# FOX_HTOL_test_1_0.net
KiCad netlist of a schematic drawn in EasyEDA Pro
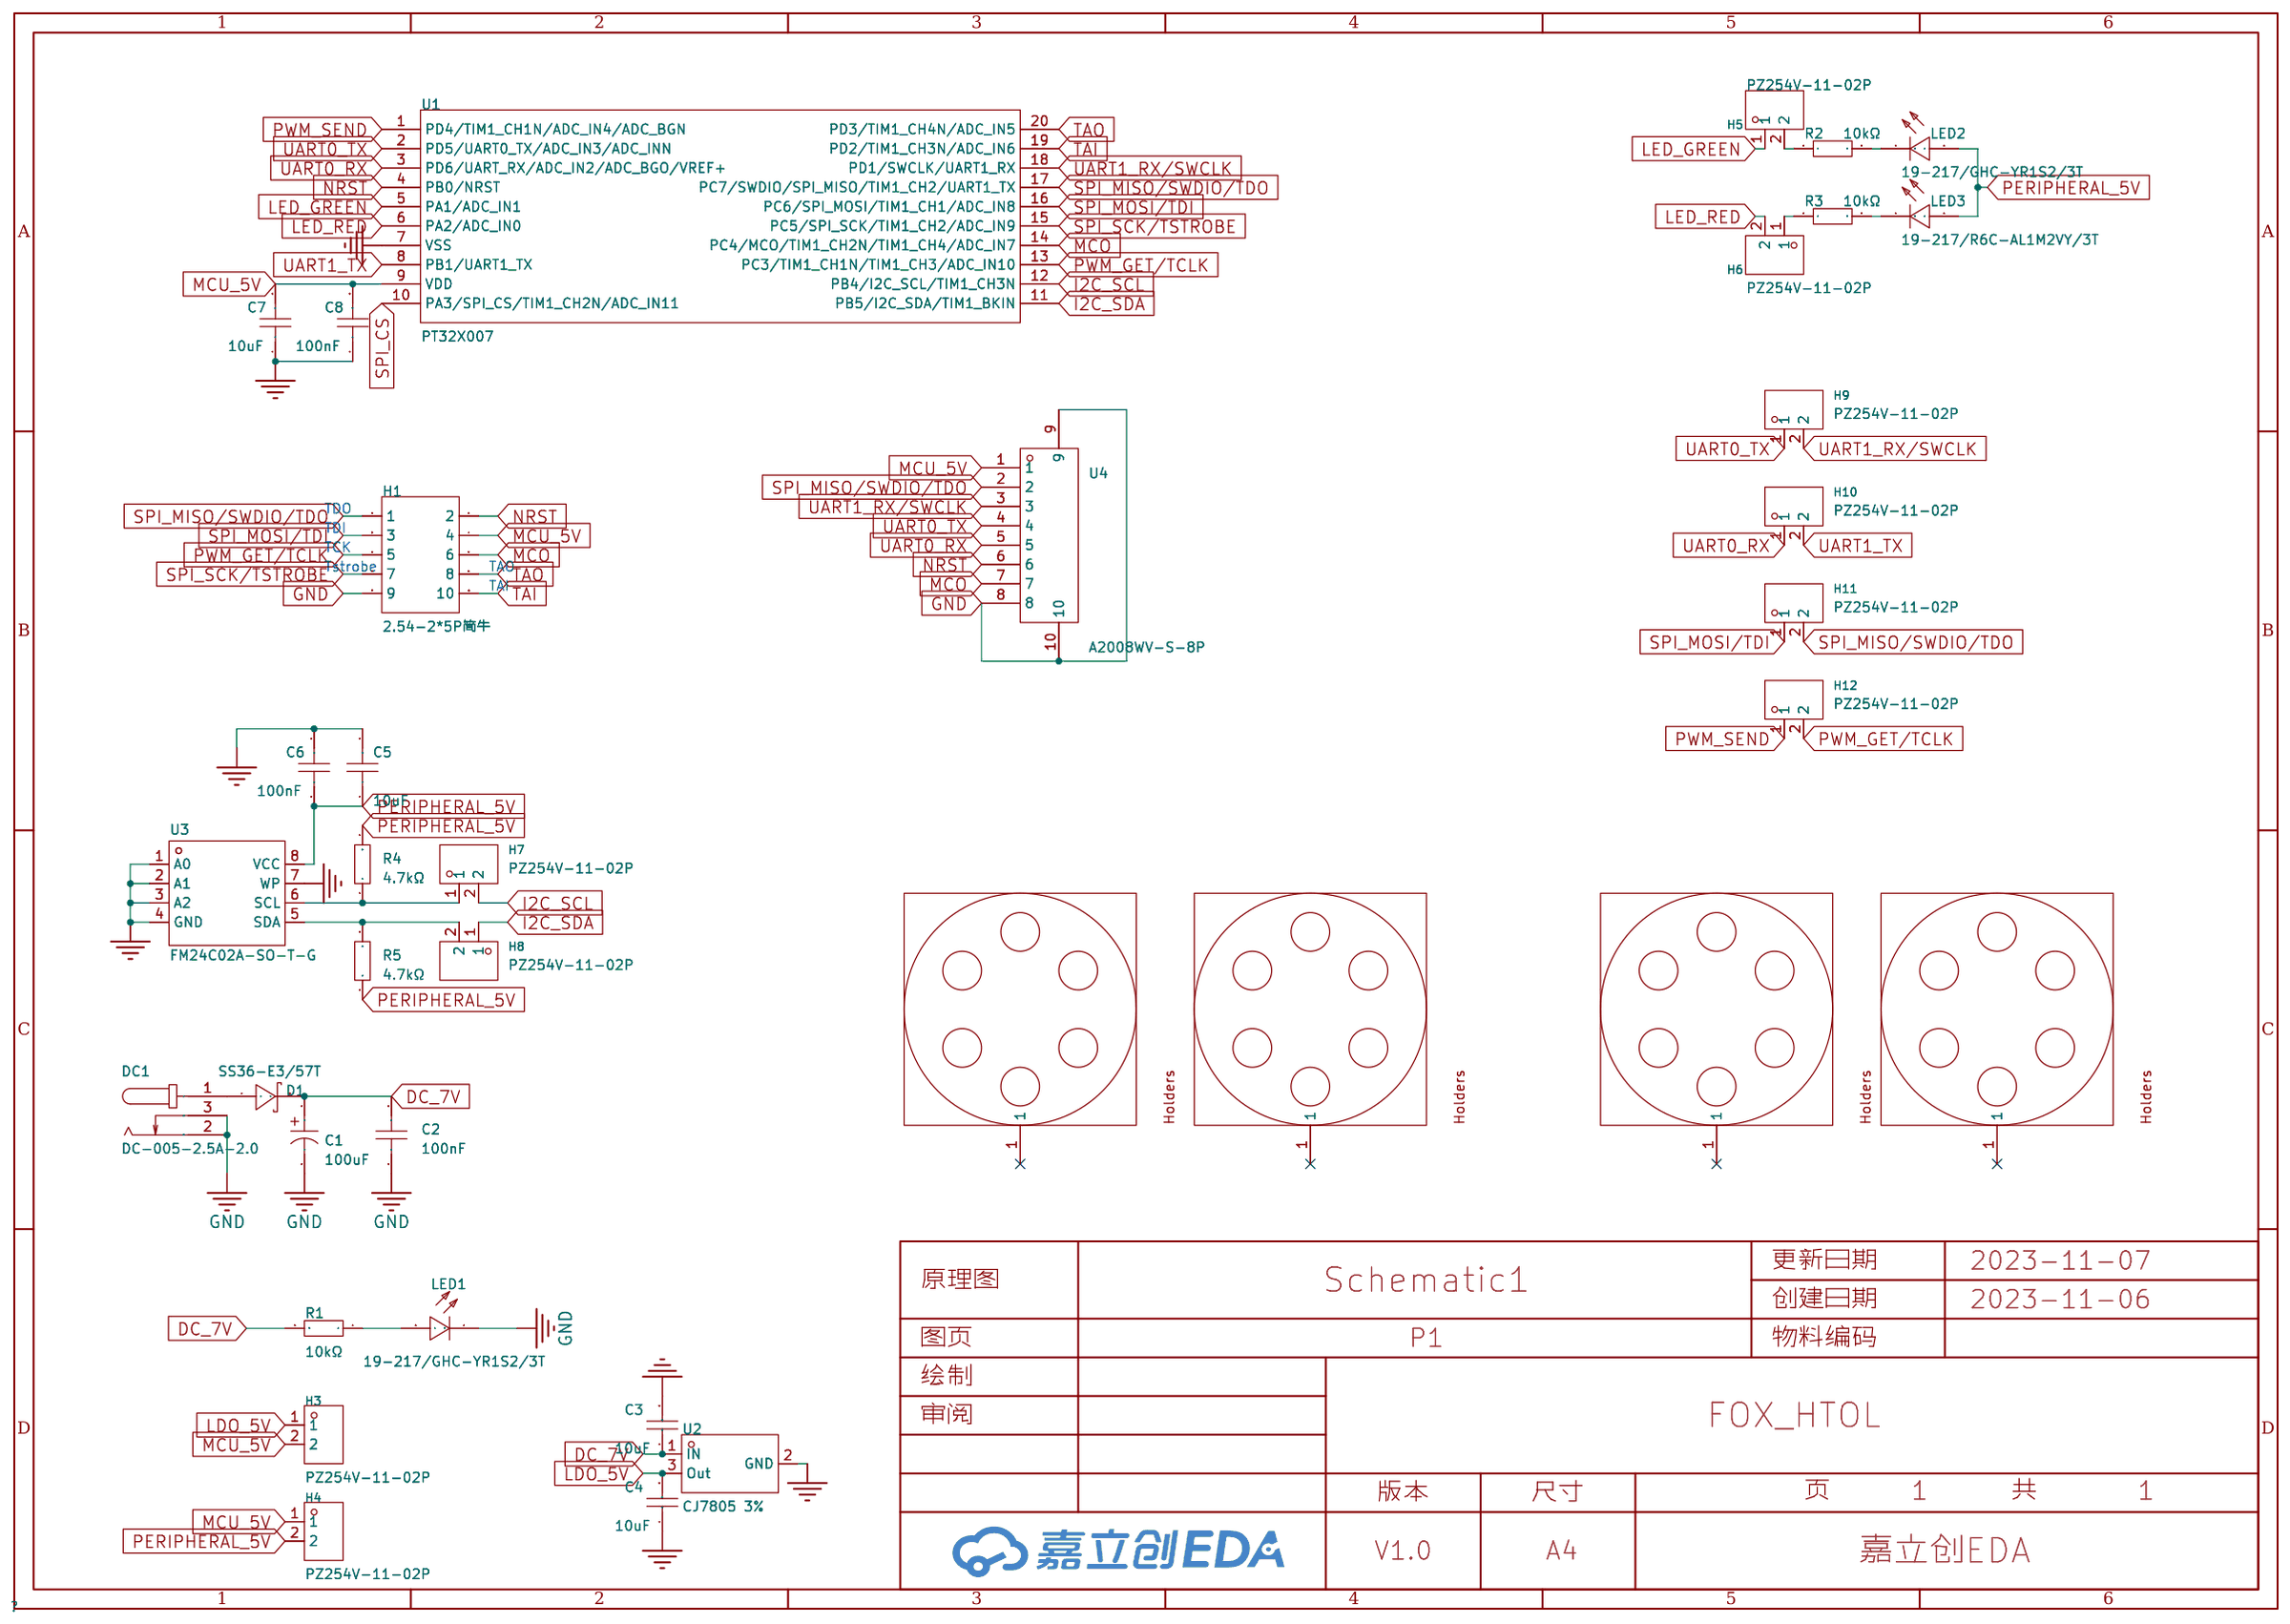
[diagram p0: schematic sheet]

(export (version "E")
  (design (tool "Eeschema 10.0.6"))
  (components
    (comp (ref "C1")
      (value "100uF")
      (footprint "easyedapro:CAP-SMD_BD6.3-L6.6-W6.6-LS7.6-FD-1")
      (description "容值:100uF;额定电压:35V;电容体直径:-;电容体长度:-;纹波电流:-;等效串联电阻:-;工作寿命:-;")
      (fields
        (field (name "Manufacturer Part") "RVE100UF35V67RV0072")
        (field (name "Manufacturer") "KNSCHA(科尼盛)")
      )
      (libsource (lib "easyedapro") (part "RVE100UF35V67RV0072"))
    )
    (comp (ref "C2")
      (value "100nF")
      (footprint "easyedapro:C0603")
      (description "容值:100nF;精度:±10%;额定电压:50V;材质(温度系数):X7R;")
      (fields
        (field (name "Manufacturer Part") "CL10B104KB8NNNC")
        (field (name "Manufacturer") "SAMSUNG(三星)")
      )
      (libsource (lib "easyedapro") (part "CL10B104KB8NNNC"))
    )
    (comp (ref "C3")
      (value "10uF")
      (footprint "easyedapro:C1206")
      (description "容值:10uF;精度:±10%;额定电压:50V;材质(温度系数):X5R;")
      (fields
        (field (name "Manufacturer Part") "CL31A106KBHNNNE")
        (field (name "Manufacturer") "SAMSUNG(三星)")
      )
      (libsource (lib "easyedapro") (part "CL31A106KBHNNNE"))
    )
    (comp (ref "C4")
      (value "10uF")
      (footprint "easyedapro:C1206")
      (description "容值:10uF;精度:±10%;额定电压:50V;材质(温度系数):X5R;")
      (fields
        (field (name "Manufacturer Part") "CL31A106KBHNNNE")
        (field (name "Manufacturer") "SAMSUNG(三星)")
      )
      (libsource (lib "easyedapro") (part "CL31A106KBHNNNE"))
    )
    (comp (ref "C5")
      (value "10uF")
      (footprint "easyedapro:C0603")
      (description "容值:10uF;精度:±20%;额定电压:25V;材质(温度系数):X5R;")
      (fields
        (field (name "Manufacturer Part") "CL10A106MA8NRNC")
        (field (name "Manufacturer") "SAMSUNG(三星)")
      )
      (libsource (lib "easyedapro") (part "CL10A106MA8NRNC"))
    )
    (comp (ref "C6")
      (value "100nF")
      (footprint "easyedapro:C0603")
      (description "容值:100nF;精度:±10%;额定电压:50V;材质(温度系数):X7R;")
      (fields
        (field (name "Manufacturer Part") "CC0603KRX7R9BB104")
        (field (name "Manufacturer") "YAGEO(国巨)")
      )
      (libsource (lib "easyedapro") (part "CC0603KRX7R9BB104"))
    )
    (comp (ref "C7")
      (value "10uF")
      (footprint "easyedapro:C0603")
      (description "容值:10uF;精度:±20%;额定电压:25V;材质(温度系数):X5R;")
      (fields
        (field (name "Manufacturer Part") "CL10A106MA8NRNC")
        (field (name "Manufacturer") "SAMSUNG(三星)")
      )
      (libsource (lib "easyedapro") (part "CL10A106MA8NRNC"))
    )
    (comp (ref "C8")
      (value "100nF")
      (footprint "easyedapro:C0603")
      (description "容值:100nF;精度:±10%;额定电压:50V;材质(温度系数):X7R;")
      (fields
        (field (name "Manufacturer Part") "CC0603KRX7R9BB104")
        (field (name "Manufacturer") "YAGEO(国巨)")
      )
      (libsource (lib "easyedapro") (part "CC0603KRX7R9BB104"))
    )
    (comp (ref "D1")
      (value "SS36-E3/57T")
      (footprint "easyedapro:SMC_L7.1-W6.2-LS8.1-R-RD")
      (description "直流反向耐压（Vr）:60V;平均整流电流（Io）:3A;正向压降（Vf）:750mV @ 3A;")
      (fields (field (name "Manufacturer") "VISHAY(威世)"))
      (libsource (lib "easyedapro") (part "SS36-E3/57T"))
    )
    (comp (ref "DC1")
      (value "DC-005-2.5A-2.0")
      (footprint "easyedapro:CONN-TH_DC-005-2.5A-2.0")
      (fields (field (name "Manufacturer") "XKB Connectivity(中国星坤)"))
      (libsource (lib "easyedapro") (part "DC-005-2.5A-2.0"))
    )
    (comp (ref "H1")
      (value "2.54-2*5P简牛")
      (footprint "easyedapro:IDC-TH_10P-P2.54_C5665")
      (description "连接器类型:简牛座;每排PIN数:5;排数:2;间距:2.54mm;行距:2.54mm;封装形式:直插;触头材质:-;触头镀层:-;")
      (fields (field (name "Manufacturer") "BOOMELE(博穆精密)"))
      (libsource (lib "easyedapro") (part "HDR-IDC-2.54-2X5P"))
    )
    (comp (ref "H3")
      (value "PZ254V-11-02P")
      (footprint "easyedapro:HDR-TH_2P-P2.54-V-M")
      (fields (field (name "Manufacturer") "XFCN(兴飞)"))
      (libsource (lib "easyedapro") (part "PZ254V-11-02P"))
    )
    (comp (ref "H4")
      (value "PZ254V-11-02P")
      (footprint "easyedapro:HDR-TH_2P-P2.54-V-M")
      (fields (field (name "Manufacturer") "XFCN(兴飞)"))
      (libsource (lib "easyedapro") (part "PZ254V-11-02P"))
    )
    (comp (ref "H5")
      (value "PZ254V-11-02P")
      (footprint "easyedapro:HDR-TH_2P-P2.54-V-M")
      (fields (field (name "Manufacturer") "XFCN(兴飞)"))
      (libsource (lib "easyedapro") (part "PZ254V-11-02P"))
    )
    (comp (ref "H6")
      (value "PZ254V-11-02P")
      (footprint "easyedapro:HDR-TH_2P-P2.54-V-M")
      (fields (field (name "Manufacturer") "XFCN(兴飞)"))
      (libsource (lib "easyedapro") (part "PZ254V-11-02P"))
    )
    (comp (ref "H7")
      (value "PZ254V-11-02P")
      (footprint "easyedapro:HDR-TH_2P-P2.54-V-M")
      (fields (field (name "Manufacturer") "XFCN(兴飞)"))
      (libsource (lib "easyedapro") (part "PZ254V-11-02P"))
    )
    (comp (ref "H8")
      (value "PZ254V-11-02P")
      (footprint "easyedapro:HDR-TH_2P-P2.54-V-M")
      (fields (field (name "Manufacturer") "XFCN(兴飞)"))
      (libsource (lib "easyedapro") (part "PZ254V-11-02P"))
    )
    (comp (ref "H9")
      (value "PZ254V-11-02P")
      (footprint "easyedapro:HDR-TH_2P-P2.54-V-M")
      (fields (field (name "Manufacturer") "XFCN(兴飞)"))
      (libsource (lib "easyedapro") (part "PZ254V-11-02P"))
    )
    (comp (ref "H10")
      (value "PZ254V-11-02P")
      (footprint "easyedapro:HDR-TH_2P-P2.54-V-M")
      (fields (field (name "Manufacturer") "XFCN(兴飞)"))
      (libsource (lib "easyedapro") (part "PZ254V-11-02P"))
    )
    (comp (ref "H11")
      (value "PZ254V-11-02P")
      (footprint "easyedapro:HDR-TH_2P-P2.54-V-M")
      (fields (field (name "Manufacturer") "XFCN(兴飞)"))
      (libsource (lib "easyedapro") (part "PZ254V-11-02P"))
    )
    (comp (ref "H12")
      (value "PZ254V-11-02P")
      (footprint "easyedapro:HDR-TH_2P-P2.54-V-M")
      (fields (field (name "Manufacturer") "XFCN(兴飞)"))
      (libsource (lib "easyedapro") (part "PZ254V-11-02P"))
    )
    (comp (ref "J2")
      (value "~")
      (footprint "easyedapro:DEMO板安装孔")
      (libsource (lib "easyedapro") (part "螺孔_3.1X6MM"))
    )
    (comp (ref "J3")
      (value "~")
      (footprint "easyedapro:DEMO板安装孔")
      (libsource (lib "easyedapro") (part "螺孔_3.1X6MM"))
    )
    (comp (ref "J4")
      (value "~")
      (footprint "easyedapro:DEMO板安装孔")
      (libsource (lib "easyedapro") (part "螺孔_3.1X6MM"))
    )
    (comp (ref "J5")
      (value "~")
      (footprint "easyedapro:DEMO板安装孔")
      (libsource (lib "easyedapro") (part "螺孔_3.1X6MM"))
    )
    (comp (ref "LED1")
      (value "19-217/GHC-YR1S2/3T")
      (footprint "easyedapro:LED0603-RD")
      (fields (field (name "Manufacturer") "EVERLIGHT(亿光)"))
      (libsource (lib "easyedapro") (part "19-217/GHC-YR1S2/3T"))
    )
    (comp (ref "LED2")
      (value "19-217/GHC-YR1S2/3T")
      (footprint "easyedapro:LED0603-RD")
      (fields (field (name "Manufacturer") "EVERLIGHT(亿光)"))
      (libsource (lib "easyedapro") (part "19-217/GHC-YR1S2/3T"))
    )
    (comp (ref "LED3")
      (value "19-217/R6C-AL1M2VY/3T")
      (footprint "easyedapro:LED0603-RD")
      (description "发光颜色:红灯;二极管配置:-;透镜颜色:无色透明;主波长:617.5nm;色温:-;功率:60mW;发光角度:120°;安装方式:-;工作温度:-40°C~+85°C;")
      (fields (field (name "Manufacturer") "EVERLIGHT(亿光)"))
      (libsource (lib "easyedapro") (part "19-217/R6C-AL1M2VY/3T"))
    )
    (comp (ref "R1")
      (value "10kΩ")
      (footprint "easyedapro:R0603")
      (description "电阻类型:厚膜电阻;阻值:10kΩ;精度:±1%;功率:100mW;温度系数:±100ppm/℃;最大工作电压:75V;工作温度范围:-55℃~+155℃;")
      (fields
        (field (name "Manufacturer Part") "0603WAF1002T5E")
        (field (name "Manufacturer") "UNI-ROYAL(厚声)")
      )
      (libsource (lib "easyedapro") (part "0603WAF1002T5E"))
    )
    (comp (ref "R2")
      (value "10kΩ")
      (footprint "easyedapro:R0603")
      (description "电阻类型:厚膜电阻;阻值:10kΩ;精度:±1%;功率:100mW;")
      (fields
        (field (name "Manufacturer Part") "0603WAF1002T5E")
        (field (name "Manufacturer") "UNI-ROYAL(厚声)")
      )
      (libsource (lib "easyedapro") (part "0603WAF1002T5E"))
    )
    (comp (ref "R3")
      (value "10kΩ")
      (footprint "easyedapro:R0603")
      (description "电阻类型:厚膜电阻;阻值:10kΩ;精度:±1%;功率:100mW;")
      (fields
        (field (name "Manufacturer Part") "0603WAF1002T5E")
        (field (name "Manufacturer") "UNI-ROYAL(厚声)")
      )
      (libsource (lib "easyedapro") (part "0603WAF1002T5E"))
    )
    (comp (ref "R4")
      (value "4.7kΩ")
      (footprint "easyedapro:R0603")
      (description "电阻类型:厚膜电阻;阻值:4.7kΩ;精度:±1%;功率:100mW;温度系数:±100ppm/°C;")
      (fields
        (field (name "Manufacturer Part") "0603WAF4701T5E")
        (field (name "Manufacturer") "UNI-ROYAL(厚声)")
      )
      (libsource (lib "easyedapro") (part "0603WAF4701T5E"))
    )
    (comp (ref "R5")
      (value "4.7kΩ")
      (footprint "easyedapro:R0603")
      (description "电阻类型:厚膜电阻;阻值:4.7kΩ;精度:±1%;功率:100mW;温度系数:±100ppm/°C;")
      (fields
        (field (name "Manufacturer Part") "0603WAF4701T5E")
        (field (name "Manufacturer") "UNI-ROYAL(厚声)")
      )
      (libsource (lib "easyedapro") (part "0603WAF4701T5E"))
    )
    (comp (ref "U1")
      (value "PT32X007")
      (footprint "easyedapro:TSSOP-20_L6.5-W4.4-P0.65-LS6.4-BL")
      (libsource (lib "easyedapro") (part "PT32X007"))
    )
    (comp (ref "U2")
      (value "CJ7805 3%")
      (footprint "easyedapro:TO-252-2_L6.6-W6.1-P4.58-LS10.1-BR-CW")
      (description "输出类型:固定;输出极性:正;最大输入电压:35V;输出电压:5V;输出电流:1.5A;")
      (fields (field (name "Manufacturer") "CJ(江苏长电/长晶)"))
      (libsource (lib "easyedapro") (part "CJ7805 3%"))
    )
    (comp (ref "U3")
      (value "FM24C02A-SO-T-G")
      (footprint "easyedapro:SOP-8_L5.0-W4.0-P1.27-LS6.2-BL")
      (description "2-Kbit(256 x 8bit)，I2C接口，工作电压：1.7V to 5.5V")
      (fields (field (name "Manufacturer") "FM(复旦微)"))
      (libsource (lib "easyedapro") (part "FM24C02A-SO-TR"))
    )
    (comp (ref "U4")
      (value "A2008WV-S-8P")
      (footprint "easyedapro:CONN-SMD_A2008WV-S-8P")
      (description "参考系列:PH;间距:2mm;插针结构:1x8P;排数:1;每排PIN数:8;行距:-;安装方式:-;触头材质:黄铜;")
      (fields (field (name "Manufacturer") "CJT(长江连接器)"))
      (libsource (lib "easyedapro") (part "A2008WV-S-8P"))
    )
  )
  (nets
    (net (code "1") (name "DC_7V") (class "Default")
      (node (ref "C1") (pin "1") (pinfunction "1_1") (pintype "input"))
      (node (ref "C2") (pin "2") (pinfunction "2_2") (pintype "input"))
      (node (ref "C3") (pin "1") (pinfunction "1_1") (pintype "input"))
      (node (ref "D1") (pin "2") (pinfunction "K_2") (pintype "input"))
      (node (ref "R1") (pin "2") (pinfunction "2_2") (pintype "input"))
      (node (ref "U2") (pin "1") (pinfunction "IN_1") (pintype "input"))
    )
    (net (code "2") (name "GND") (class "Default")
      (node (ref "C1") (pin "2") (pinfunction "2_2") (pintype "input"))
      (node (ref "C2") (pin "1") (pinfunction "1_1") (pintype "input"))
      (node (ref "C3") (pin "2") (pinfunction "2_2") (pintype "input"))
      (node (ref "C4") (pin "1") (pinfunction "1_1") (pintype "input"))
      (node (ref "C5") (pin "2") (pinfunction "2_2") (pintype "input"))
      (node (ref "C6") (pin "2") (pinfunction "2_2") (pintype "input"))
      (node (ref "C7") (pin "1") (pinfunction "1_1") (pintype "input"))
      (node (ref "C8") (pin "1") (pinfunction "1_1") (pintype "input"))
      (node (ref "DC1") (pin "2") (pinfunction "2_2") (pintype "input"))
      (node (ref "DC1") (pin "3") (pinfunction "3_3") (pintype "input"))
      (node (ref "H1") (pin "9") (pinfunction "9_9") (pintype "input"))
      (node (ref "LED1") (pin "1") (pinfunction "C_1") (pintype "input"))
      (node (ref "U1") (pin "7") (pinfunction "VSS_7") (pintype "input"))
      (node (ref "U2") (pin "2") (pinfunction "GND_2") (pintype "input"))
      (node (ref "U3") (pin "1") (pinfunction "A0_1") (pintype "unspecified"))
      (node (ref "U3") (pin "2") (pinfunction "A1_2") (pintype "unspecified"))
      (node (ref "U3") (pin "3") (pinfunction "A2_3") (pintype "unspecified"))
      (node (ref "U3") (pin "4") (pinfunction "GND_4") (pintype "unspecified"))
      (node (ref "U3") (pin "7") (pinfunction "WP_7") (pintype "unspecified"))
      (node (ref "U4") (pin "10") (pinfunction "10_10") (pintype "input"))
      (node (ref "U4") (pin "8") (pinfunction "8_8") (pintype "input"))
      (node (ref "U4") (pin "9") (pinfunction "9_9") (pintype "input"))
    )
    (net (code "3") (name "I2C_SCL") (class "Default")
      (node (ref "H7") (pin "2") (pinfunction "2_2") (pintype "input"))
      (node (ref "U1") (pin "12") (pinfunction "PB4/I2C_SCL/TIM1_CH3N_12") (pintype "input"))
    )
    (net (code "4") (name "I2C_SDA") (class "Default")
      (node (ref "H8") (pin "1") (pinfunction "1_1") (pintype "input"))
      (node (ref "U1") (pin "11") (pinfunction "PB5/I2C_SDA/TIM1_BKIN_11") (pintype "input"))
    )
    (net (code "5") (name "LDO_5V") (class "Default")
      (node (ref "C4") (pin "2") (pinfunction "2_2") (pintype "input"))
      (node (ref "H3") (pin "1") (pinfunction "1_1") (pintype "input"))
      (node (ref "U2") (pin "3") (pinfunction "Out_3") (pintype "input"))
    )
    (net (code "6") (name "LED_GREEN") (class "Default")
      (node (ref "H5") (pin "1") (pinfunction "1_1") (pintype "input"))
      (node (ref "U1") (pin "5") (pinfunction "PA1/ADC_IN1_5") (pintype "input"))
    )
    (net (code "7") (name "LED_RED") (class "Default")
      (node (ref "H6") (pin "2") (pinfunction "2_2") (pintype "input"))
      (node (ref "U1") (pin "6") (pinfunction "PA2/ADC_IN0_6") (pintype "input"))
    )
    (net (code "8") (name "MCO") (class "Default")
      (node (ref "H1") (pin "6") (pinfunction "6_6") (pintype "input"))
      (node (ref "U1") (pin "14") (pinfunction "PC4/MCO/TIM1_CH2N/TIM1_CH4/ADC_IN7_14") (pintype "input"))
      (node (ref "U4") (pin "7") (pinfunction "7_7") (pintype "input"))
    )
    (net (code "9") (name "MCU_5V") (class "Default")
      (node (ref "C7") (pin "2") (pinfunction "2_2") (pintype "input"))
      (node (ref "C8") (pin "2") (pinfunction "2_2") (pintype "input"))
      (node (ref "H1") (pin "4") (pinfunction "4_4") (pintype "input"))
      (node (ref "H3") (pin "2") (pinfunction "2_2") (pintype "input"))
      (node (ref "H4") (pin "1") (pinfunction "1_1") (pintype "input"))
      (node (ref "U1") (pin "9") (pinfunction "VDD_9") (pintype "input"))
      (node (ref "U4") (pin "1") (pinfunction "1_1") (pintype "input"))
    )
    (net (code "10") (name "NRST") (class "Default")
      (node (ref "H1") (pin "2") (pinfunction "2_2") (pintype "input"))
      (node (ref "U1") (pin "4") (pinfunction "PB0/NRST_4") (pintype "input"))
      (node (ref "U4") (pin "6") (pinfunction "6_6") (pintype "input"))
    )
    (net (code "11") (name "Net-(D1-A)") (class "Default")
      (node (ref "D1") (pin "1") (pinfunction "A_1") (pintype "input"))
      (node (ref "DC1") (pin "1") (pinfunction "1_1") (pintype "input"))
    )
    (net (code "12") (name "Net-(H5-Pad2)") (class "Default")
      (node (ref "H5") (pin "2") (pinfunction "2_2") (pintype "input"))
      (node (ref "R2") (pin "1") (pinfunction "1_1") (pintype "input"))
    )
    (net (code "13") (name "Net-(H6-Pad1)") (class "Default")
      (node (ref "H6") (pin "1") (pinfunction "1_1") (pintype "input"))
      (node (ref "R3") (pin "1") (pinfunction "1_1") (pintype "input"))
    )
    (net (code "14") (name "Net-(LED1-A)") (class "Default")
      (node (ref "LED1") (pin "2") (pinfunction "A_2") (pintype "input"))
      (node (ref "R1") (pin "1") (pinfunction "1_1") (pintype "input"))
    )
    (net (code "15") (name "Net-(LED2-C)") (class "Default")
      (node (ref "LED2") (pin "1") (pinfunction "C_1") (pintype "input"))
      (node (ref "R2") (pin "2") (pinfunction "2_2") (pintype "input"))
    )
    (net (code "16") (name "Net-(LED3-C)") (class "Default")
      (node (ref "LED3") (pin "1") (pinfunction "C_1") (pintype "input"))
      (node (ref "R3") (pin "2") (pinfunction "2_2") (pintype "input"))
    )
    (net (code "17") (name "Net-(U3-SCL)") (class "Default")
      (node (ref "H7") (pin "1") (pinfunction "1_1") (pintype "input"))
      (node (ref "R4") (pin "1") (pinfunction "1_1") (pintype "input"))
      (node (ref "U3") (pin "6") (pinfunction "SCL_6") (pintype "unspecified"))
    )
    (net (code "18") (name "Net-(U3-SDA)") (class "Default")
      (node (ref "H8") (pin "2") (pinfunction "2_2") (pintype "input"))
      (node (ref "R5") (pin "2") (pinfunction "2_2") (pintype "input"))
      (node (ref "U3") (pin "5") (pinfunction "SDA_5") (pintype "unspecified"))
    )
    (net (code "19") (name "PERIPHERAL_5V") (class "Default")
      (node (ref "C5") (pin "1") (pinfunction "1_1") (pintype "input"))
      (node (ref "C6") (pin "1") (pinfunction "1_1") (pintype "input"))
      (node (ref "H4") (pin "2") (pinfunction "2_2") (pintype "input"))
      (node (ref "LED2") (pin "2") (pinfunction "A_2") (pintype "input"))
      (node (ref "LED3") (pin "2") (pinfunction "A_2") (pintype "input"))
      (node (ref "R4") (pin "2") (pinfunction "2_2") (pintype "input"))
      (node (ref "R5") (pin "1") (pinfunction "1_1") (pintype "input"))
      (node (ref "U3") (pin "8") (pinfunction "VCC_8") (pintype "unspecified"))
    )
    (net (code "20") (name "PWM_GET{slash}TCLK") (class "Default")
      (node (ref "H1") (pin "5") (pinfunction "5_5") (pintype "input"))
      (node (ref "H12") (pin "2") (pinfunction "2_2") (pintype "input"))
      (node (ref "U1") (pin "13") (pinfunction "PC3/TIM1_CH1N/TIM1_CH3/ADC_IN10_13") (pintype "input"))
    )
    (net (code "21") (name "PWM_SEND") (class "Default")
      (node (ref "H12") (pin "1") (pinfunction "1_1") (pintype "input"))
      (node (ref "U1") (pin "1") (pinfunction "PD4/TIM1_CH1N/ADC_IN4/ADC_BGN_1") (pintype "input"))
    )
    (net (code "22") (name "SPI_CS") (class "Default")
      (node (ref "U1") (pin "10") (pinfunction "PA3/SPI_CS/TIM1_CH2N/ADC_IN11_10") (pintype "input"))
    )
    (net (code "23") (name "SPI_MISO{slash}SWDIO{slash}TDO") (class "Default")
      (node (ref "H1") (pin "1") (pinfunction "1_1") (pintype "input"))
      (node (ref "H11") (pin "2") (pinfunction "2_2") (pintype "input"))
      (node (ref "U1") (pin "17") (pinfunction "PC7/SWDIO/SPI_MISO/TIM1_CH2/UART1_TX_17") (pintype "input"))
      (node (ref "U4") (pin "2") (pinfunction "2_2") (pintype "input"))
    )
    (net (code "24") (name "SPI_MOSI{slash}TDI") (class "Default")
      (node (ref "H1") (pin "3") (pinfunction "3_3") (pintype "input"))
      (node (ref "H11") (pin "1") (pinfunction "1_1") (pintype "input"))
      (node (ref "U1") (pin "16") (pinfunction "PC6/SPI_MOSI/TIM1_CH1/ADC_IN8_16") (pintype "input"))
    )
    (net (code "25") (name "SPI_SCK{slash}TSTROBE") (class "Default")
      (node (ref "H1") (pin "7") (pinfunction "7_7") (pintype "input"))
      (node (ref "U1") (pin "15") (pinfunction "PC5/SPI_SCK/TIM1_CH2/ADC_IN9_15") (pintype "input"))
    )
    (net (code "26") (name "TAI") (class "Default")
      (node (ref "H1") (pin "10") (pinfunction "10_10") (pintype "input"))
      (node (ref "U1") (pin "19") (pinfunction "PD2/TIM1_CH3N/ADC_IN6_19") (pintype "input"))
    )
    (net (code "27") (name "TAO") (class "Default")
      (node (ref "H1") (pin "8") (pinfunction "8_8") (pintype "input"))
      (node (ref "U1") (pin "20") (pinfunction "PD3/TIM1_CH4N/ADC_IN5_20") (pintype "input"))
    )
    (net (code "28") (name "UART0_RX") (class "Default")
      (node (ref "H10") (pin "1") (pinfunction "1_1") (pintype "input"))
      (node (ref "U1") (pin "3") (pinfunction "PD6/UART_RX/ADC_IN2/ADC_BGO/VREF+_3") (pintype "input"))
      (node (ref "U4") (pin "5") (pinfunction "5_5") (pintype "input"))
    )
    (net (code "29") (name "UART0_TX") (class "Default")
      (node (ref "H9") (pin "1") (pinfunction "1_1") (pintype "input"))
      (node (ref "U1") (pin "2") (pinfunction "PD5/UART0_TX/ADC_IN3/ADC_INN_2") (pintype "input"))
      (node (ref "U4") (pin "4") (pinfunction "4_4") (pintype "input"))
    )
    (net (code "30") (name "UART1_RX{slash}SWCLK") (class "Default")
      (node (ref "H9") (pin "2") (pinfunction "2_2") (pintype "input"))
      (node (ref "U1") (pin "18") (pinfunction "PD1/SWCLK/UART1_RX_18") (pintype "input"))
      (node (ref "U4") (pin "3") (pinfunction "3_3") (pintype "input"))
    )
    (net (code "31") (name "UART1_TX") (class "Default")
      (node (ref "H10") (pin "2") (pinfunction "2_2") (pintype "input"))
      (node (ref "U1") (pin "8") (pinfunction "PB1/UART1_TX_8") (pintype "input"))
    )
    (net (code "32") (name "unconnected-(J2-Pad1)") (class "Default")
      (node (ref "J2") (pin "1") (pinfunction "1_1") (pintype "input+no_connect"))
    )
    (net (code "33") (name "unconnected-(J3-Pad1)") (class "Default")
      (node (ref "J3") (pin "1") (pinfunction "1_1") (pintype "input+no_connect"))
    )
    (net (code "34") (name "unconnected-(J4-Pad1)") (class "Default")
      (node (ref "J4") (pin "1") (pinfunction "1_1") (pintype "input+no_connect"))
    )
    (net (code "35") (name "unconnected-(J5-Pad1)") (class "Default")
      (node (ref "J5") (pin "1") (pinfunction "1_1") (pintype "input+no_connect"))
    )
  )
)
